# Copy_of_Sheet1.net
KiCad netlist of a schematic drawn in Altium Designer
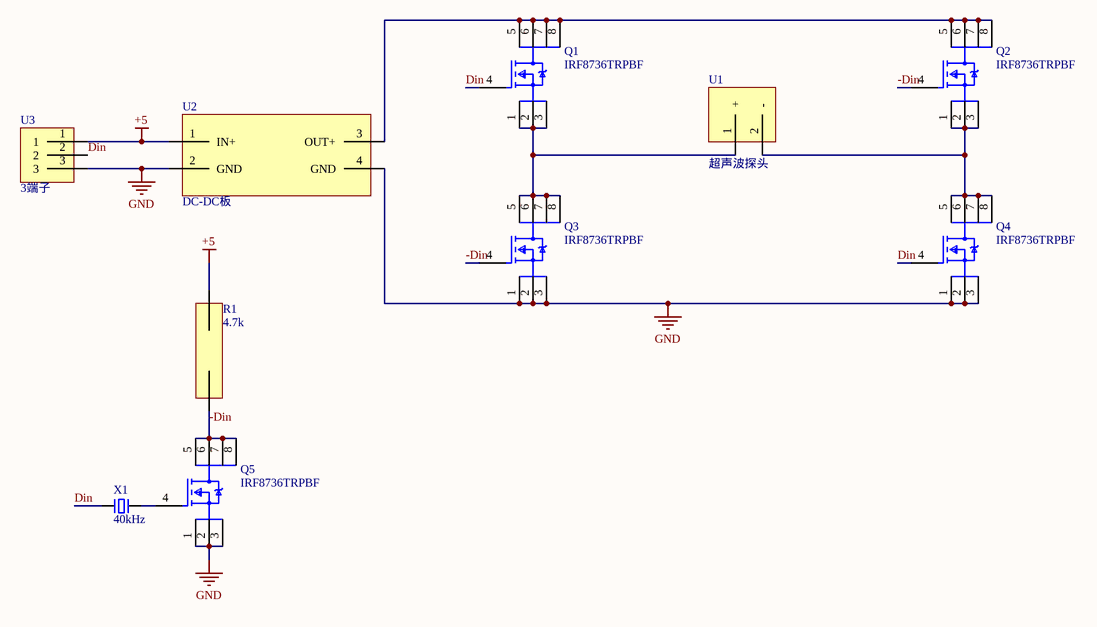
[diagram p0: Copy of Sheet1.SchDoc]

(export (version "E")
  (design (tool "Eeschema 10.0.6"))
  (components
    (comp (ref "Q1")
      (value "IRF8736TRPBF")
      (footprint "FP-PG-DSO-8-MFG")
      (description "MOSFET N-CH 30V 18A 8-SOIC")
      (fields
        (field (name "MANUFACTURER") "Infineon")
        (field (name "OCTOPART") "https://octopart.com/irf8736trpbf-infineon-65873731")
      )
      (libsource (lib "Altium Content Vault") (part "6c4379695d6b9ddabb25581bf066c8b"))
    )
    (comp (ref "Q2")
      (value "IRF8736TRPBF")
      (footprint "FP-PG-DSO-8-MFG")
      (description "MOSFET N-CH 30V 18A 8-SOIC")
      (fields
        (field (name "MANUFACTURER") "Infineon")
        (field (name "OCTOPART") "https://octopart.com/irf8736trpbf-infineon-65873731")
      )
      (libsource (lib "Altium Content Vault") (part "6c4379695d6b9ddabb25581bf066c8b"))
    )
    (comp (ref "Q3")
      (value "IRF8736TRPBF")
      (footprint "FP-PG-DSO-8-MFG")
      (description "MOSFET N-CH 30V 18A 8-SOIC")
      (fields
        (field (name "MANUFACTURER") "Infineon")
        (field (name "OCTOPART") "https://octopart.com/irf8736trpbf-infineon-65873731")
      )
      (libsource (lib "Altium Content Vault") (part "6c4379695d6b9ddabb25581bf066c8b"))
    )
    (comp (ref "Q4")
      (value "IRF8736TRPBF")
      (footprint "FP-PG-DSO-8-MFG")
      (description "MOSFET N-CH 30V 18A 8-SOIC")
      (fields
        (field (name "MANUFACTURER") "Infineon")
        (field (name "OCTOPART") "https://octopart.com/irf8736trpbf-infineon-65873731")
      )
      (libsource (lib "Altium Content Vault") (part "6c4379695d6b9ddabb25581bf066c8b"))
    )
    (comp (ref "Q5")
      (value "IRF8736TRPBF")
      (footprint "FP-PG-DSO-8-MFG")
      (description "MOSFET N-CH 30V 18A 8-SOIC")
      (fields
        (field (name "MANUFACTURER") "Infineon")
        (field (name "OCTOPART") "https://octopart.com/irf8736trpbf-infineon-65873731")
      )
      (libsource (lib "Altium Content Vault") (part "6c4379695d6b9ddabb25581bf066c8b"))
    )
    (comp (ref "R1") (value "4.7k") (footprint "0603") (libsource (lib "Schlib1") (part "0603")))
    (comp (ref "U1") (value "超声波探头") (footprint "超声波探头") (libsource (lib "Schlib1") (part "超声波探头")))
    (comp (ref "U2") (value "DC-DC板") (footprint "DC-DC板") (libsource (lib "Schlib1") (part "DC-DC板")))
    (comp (ref "U3") (value "3端子") (footprint "HDR2.54-LI-3P") (libsource (lib "Schlib1") (part "3端子")))
    (comp (ref "X1")
      (value "40kHz")
      (footprint "OSC-3x8-LI")
      (description "2脚无源脚晶振")
      (fields (field (name "版权归属") "封装库来自淘宝卖家 ID：黄晶宝石"))
      (libsource (lib "2.0 - 保险丝-晶振-光耦") (part "XTAL-2P"))
    )
  )
  (nets
    (net (code "1") (name "+5") (class "Default")
      (node (ref "R1") (pin "2") (pinfunction "2_2") (pintype "passive"))
      (node (ref "U2") (pin "1") (pinfunction "IN+_1") (pintype "passive"))
      (node (ref "U3") (pin "1") (pinfunction "1_1") (pintype "passive"))
    )
    (net (code "2") (name "/-Din") (class "Default")
      (node (ref "Q2") (pin "4") (pinfunction "G_4") (pintype "passive"))
      (node (ref "Q3") (pin "4") (pinfunction "G_4") (pintype "passive"))
      (node (ref "Q5") (pin "5") (pinfunction "D_5") (pintype "passive"))
      (node (ref "Q5") (pin "6") (pinfunction "D_6") (pintype "passive"))
      (node (ref "Q5") (pin "7") (pinfunction "D_7") (pintype "passive"))
      (node (ref "Q5") (pin "8") (pinfunction "D_8") (pintype "passive"))
      (node (ref "R1") (pin "1") (pinfunction "1_1") (pintype "passive"))
    )
    (net (code "3") (name "/Din") (class "Default")
      (node (ref "Q1") (pin "4") (pinfunction "G_4") (pintype "passive"))
      (node (ref "Q4") (pin "4") (pinfunction "G_4") (pintype "passive"))
      (node (ref "U3") (pin "2") (pinfunction "2_2") (pintype "passive"))
      (node (ref "X1") (pin "2") (pinfunction "2_2") (pintype "passive"))
    )
    (net (code "4") (name "GND") (class "Default")
      (node (ref "Q3") (pin "1") (pinfunction "S_1") (pintype "passive"))
      (node (ref "Q3") (pin "2") (pinfunction "S_2") (pintype "passive"))
      (node (ref "Q3") (pin "3") (pinfunction "S_3") (pintype "passive"))
      (node (ref "Q4") (pin "1") (pinfunction "S_1") (pintype "passive"))
      (node (ref "Q4") (pin "2") (pinfunction "S_2") (pintype "passive"))
      (node (ref "Q4") (pin "3") (pinfunction "S_3") (pintype "passive"))
      (node (ref "Q5") (pin "1") (pinfunction "S_1") (pintype "passive"))
      (node (ref "Q5") (pin "2") (pinfunction "S_2") (pintype "passive"))
      (node (ref "Q5") (pin "3") (pinfunction "S_3") (pintype "passive"))
      (node (ref "U2") (pin "2") (pinfunction "GND_2") (pintype "passive"))
      (node (ref "U2") (pin "4") (pinfunction "GND_4") (pintype "passive"))
      (node (ref "U3") (pin "3") (pinfunction "3_3") (pintype "passive"))
    )
    (net (code "5") (name "Net-(Q5-G)") (class "Default")
      (node (ref "Q5") (pin "4") (pinfunction "G_4") (pintype "passive"))
      (node (ref "X1") (pin "1") (pinfunction "1_1") (pintype "passive"))
    )
    (net (code "6") (name "Net-(U1-+)") (class "Default")
      (node (ref "Q1") (pin "1") (pinfunction "S_1") (pintype "passive"))
      (node (ref "Q1") (pin "2") (pinfunction "S_2") (pintype "passive"))
      (node (ref "Q1") (pin "3") (pinfunction "S_3") (pintype "passive"))
      (node (ref "Q3") (pin "5") (pinfunction "D_5") (pintype "passive"))
      (node (ref "Q3") (pin "6") (pinfunction "D_6") (pintype "passive"))
      (node (ref "Q3") (pin "7") (pinfunction "D_7") (pintype "passive"))
      (node (ref "Q3") (pin "8") (pinfunction "D_8") (pintype "passive"))
      (node (ref "U1") (pin "1") (pinfunction "+_1") (pintype "passive"))
    )
    (net (code "7") (name "Net-(U1--)") (class "Default")
      (node (ref "Q2") (pin "1") (pinfunction "S_1") (pintype "passive"))
      (node (ref "Q2") (pin "2") (pinfunction "S_2") (pintype "passive"))
      (node (ref "Q2") (pin "3") (pinfunction "S_3") (pintype "passive"))
      (node (ref "Q4") (pin "5") (pinfunction "D_5") (pintype "passive"))
      (node (ref "Q4") (pin "6") (pinfunction "D_6") (pintype "passive"))
      (node (ref "Q4") (pin "7") (pinfunction "D_7") (pintype "passive"))
      (node (ref "Q4") (pin "8") (pinfunction "D_8") (pintype "passive"))
      (node (ref "U1") (pin "2") (pinfunction "-_2") (pintype "passive"))
    )
    (net (code "8") (name "Net-(U2-OUT+)") (class "Default")
      (node (ref "Q1") (pin "5") (pinfunction "D_5") (pintype "passive"))
      (node (ref "Q1") (pin "6") (pinfunction "D_6") (pintype "passive"))
      (node (ref "Q1") (pin "7") (pinfunction "D_7") (pintype "passive"))
      (node (ref "Q1") (pin "8") (pinfunction "D_8") (pintype "passive"))
      (node (ref "Q2") (pin "5") (pinfunction "D_5") (pintype "passive"))
      (node (ref "Q2") (pin "6") (pinfunction "D_6") (pintype "passive"))
      (node (ref "Q2") (pin "7") (pinfunction "D_7") (pintype "passive"))
      (node (ref "Q2") (pin "8") (pinfunction "D_8") (pintype "passive"))
      (node (ref "U2") (pin "3") (pinfunction "OUT+_3") (pintype "passive"))
    )
  )
)
